# IC_555_new.net
KiCad netlist of a schematic drawn in EAGLE
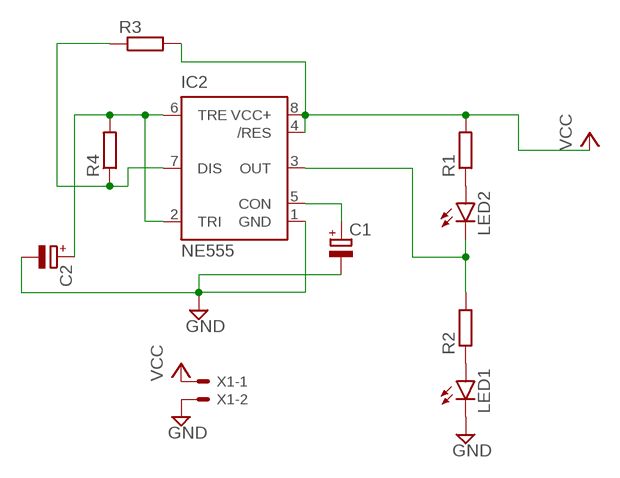
[diagram p0: schematic, sheet 1]

(export (version "E")
  (design (tool "Eeschema 10.0.6"))
  (components
    (comp (ref "C1")
      (value "CPOL-EUE2.5-6")
      (footprint "eagle-import:E2,5-6")
      (libsource (lib "eagle-import") (part "CPOL-EUE2.5-6"))
    )
    (comp (ref "C2")
      (value "CPOL-EUE2.5-6")
      (footprint "eagle-import:E2,5-6")
      (libsource (lib "eagle-import") (part "CPOL-EUE2.5-6"))
    )
    (comp (ref "IC2")
      (value "NE555")
      (footprint "eagle-import:DIL-08")
      (fields (field (name "MF") "Arrow Electronics") (field (name "MPN") "NE555N"))
      (libsource (lib "eagle-import") (part "NE555"))
    )
    (comp (ref "LED1")
      (value "LED5MM")
      (footprint "eagle-import:LED5MM")
      (libsource (lib "eagle-import") (part "LED5MM"))
    )
    (comp (ref "LED2")
      (value "LED5MM")
      (footprint "eagle-import:LED5MM")
      (libsource (lib "eagle-import") (part "LED5MM"))
    )
    (comp (ref "R1")
      (value "R-EU_0204/5")
      (footprint "eagle-import:0204_5")
      (libsource (lib "eagle-import") (part "R-EU_0204/5"))
    )
    (comp (ref "R2")
      (value "R-EU_0204/5")
      (footprint "eagle-import:0204_5")
      (libsource (lib "eagle-import") (part "R-EU_0204/5"))
    )
    (comp (ref "R3")
      (value "R-EU_0204/5")
      (footprint "eagle-import:0204_5")
      (libsource (lib "eagle-import") (part "R-EU_0204/5"))
    )
    (comp (ref "R4")
      (value "R-EU_0204/5")
      (footprint "eagle-import:0204_5")
      (libsource (lib "eagle-import") (part "R-EU_0204/5"))
    )
    (comp (ref "X1")
      (value "JST-XH-02-PIN-ROUND-PAD")
      (footprint "eagle-import:JST-XH-02-PACKAGE-ROUND-PAD")
      (libsource (lib "eagle-import") (part "JST-XH-02-PIN-ROUND-PAD"))
    )
  )
  (nets
    (net (code "1") (name "GND") (class "Default")
      (node (ref "C1") (pin "-") (pinfunction "-_-") (pintype "passive"))
      (node (ref "C2") (pin "-") (pinfunction "-_-") (pintype "passive"))
      (node (ref "IC2") (pin "1") (pinfunction "GND_1") (pintype "power_in"))
      (node (ref "LED1") (pin "K") (pinfunction "C_K") (pintype "passive"))
      (node (ref "X1") (pin "2") (pinfunction "S_2") (pintype "passive"))
    )
    (net (code "2") (name "Net-(IC2-CON)") (class "Default")
      (node (ref "C1") (pin "+") (pinfunction "+_+") (pintype "passive"))
      (node (ref "IC2") (pin "5") (pinfunction "CON_5") (pintype "input"))
    )
    (net (code "3") (name "Net-(IC2-DIS)") (class "Default")
      (node (ref "IC2") (pin "7") (pinfunction "DIS_7") (pintype "input"))
      (node (ref "R3") (pin "1") (pinfunction "1_1") (pintype "passive"))
      (node (ref "R4") (pin "1") (pinfunction "1_1") (pintype "passive"))
    )
    (net (code "4") (name "Net-(IC2-OUT)") (class "Default")
      (node (ref "IC2") (pin "3") (pinfunction "OUT_3") (pintype "output"))
      (node (ref "LED2") (pin "K") (pinfunction "C_K") (pintype "passive"))
      (node (ref "R2") (pin "2") (pinfunction "2_2") (pintype "passive"))
    )
    (net (code "5") (name "Net-(IC2-TRE)") (class "Default")
      (node (ref "C2") (pin "+") (pinfunction "+_+") (pintype "passive"))
      (node (ref "IC2") (pin "2") (pinfunction "TRI_2") (pintype "input"))
      (node (ref "IC2") (pin "6") (pinfunction "TRE_6") (pintype "input"))
      (node (ref "R4") (pin "2") (pinfunction "2_2") (pintype "passive"))
    )
    (net (code "6") (name "Net-(LED1-PadA)") (class "Default")
      (node (ref "LED1") (pin "A") (pinfunction "A_A") (pintype "passive"))
      (node (ref "R2") (pin "1") (pinfunction "1_1") (pintype "passive"))
    )
    (net (code "7") (name "Net-(LED2-PadA)") (class "Default")
      (node (ref "LED2") (pin "A") (pinfunction "A_A") (pintype "passive"))
      (node (ref "R1") (pin "1") (pinfunction "1_1") (pintype "passive"))
    )
    (net (code "8") (name "VCC") (class "Default")
      (node (ref "IC2") (pin "4") (pinfunction "/RES_4") (pintype "input"))
      (node (ref "IC2") (pin "8") (pinfunction "VCC+_8") (pintype "power_in"))
      (node (ref "R1") (pin "2") (pinfunction "2_2") (pintype "passive"))
      (node (ref "R3") (pin "2") (pinfunction "2_2") (pintype "passive"))
      (node (ref "X1") (pin "1") (pinfunction "S_1") (pintype "passive"))
    )
  )
)
